# Voltage_Regulator_Design.net
KiCad netlist of a schematic drawn in EAGLE
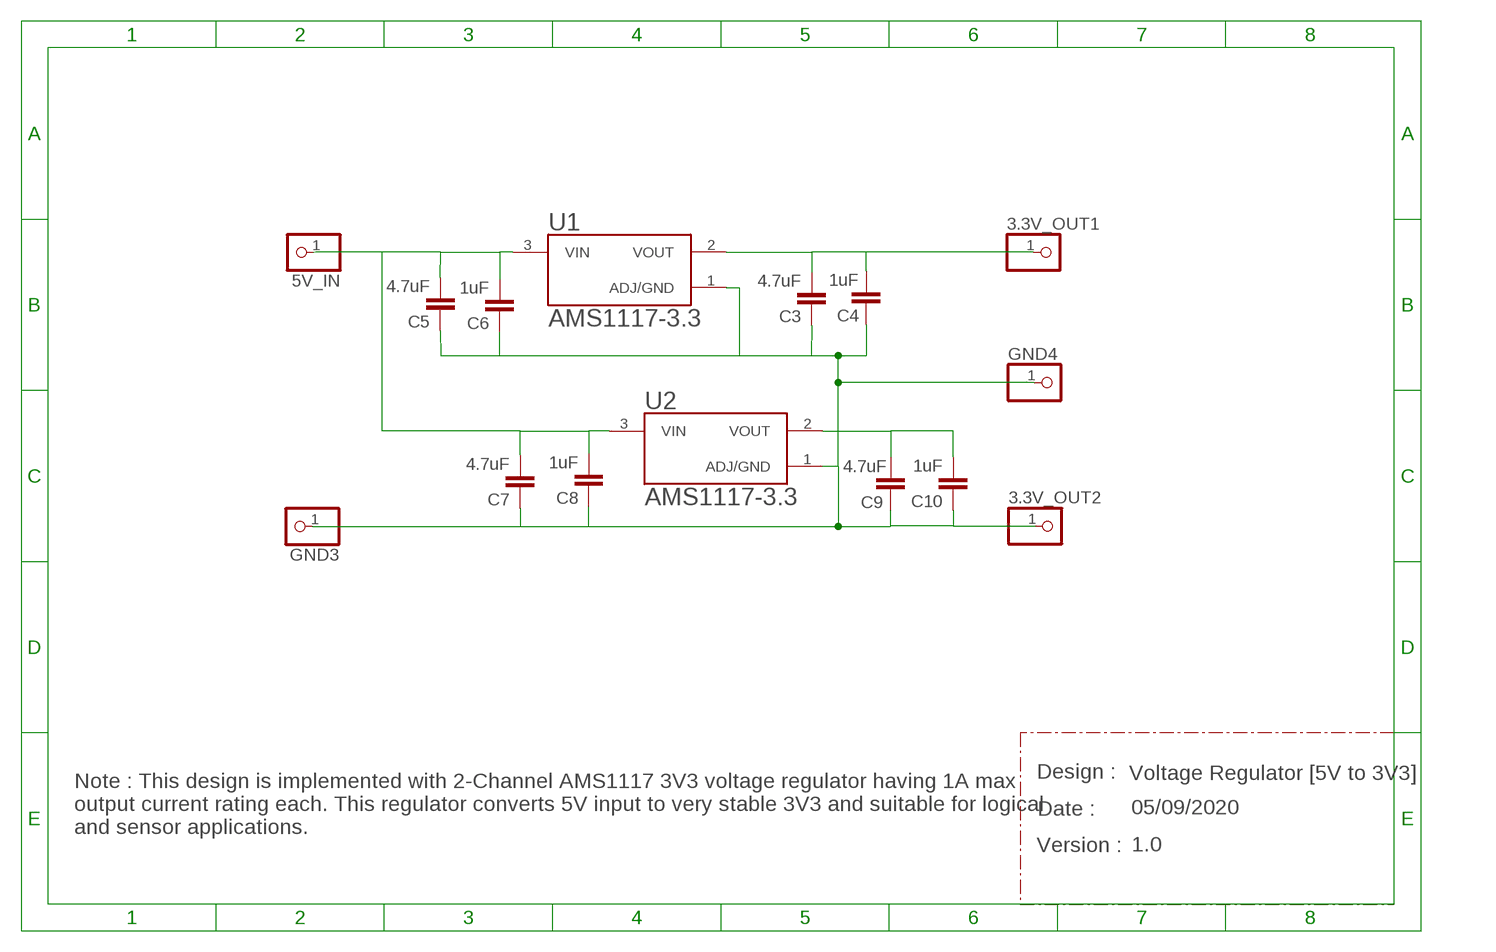
[diagram p0: schematic, sheet 1]

(export (version "E")
  (design (tool "Eeschema 10.0.6"))
  (components
    (comp (ref "3.3V_OUT1")
      (value "PINHD-1X1")
      (footprint "eagle-import:1X01")
      (libsource (lib "eagle-import") (part "PINHD-1X1"))
    )
    (comp (ref "3.3V_OUT2")
      (value "PINHD-1X1")
      (footprint "eagle-import:1X01")
      (libsource (lib "eagle-import") (part "PINHD-1X1"))
    )
    (comp (ref "5V_IN")
      (value "PINHD-1X1")
      (footprint "eagle-import:1X01")
      (libsource (lib "eagle-import") (part "PINHD-1X1"))
    )
    (comp (ref "C3")
      (value "4.7uF")
      (footprint "eagle-import:C0805")
      (libsource (lib "eagle-import") (part "C-EUC0805"))
    )
    (comp (ref "C4")
      (value "1uF")
      (footprint "eagle-import:C0805")
      (libsource (lib "eagle-import") (part "C-EUC0805"))
    )
    (comp (ref "C5")
      (value "4.7uF")
      (footprint "eagle-import:C0805")
      (libsource (lib "eagle-import") (part "C-EUC0805"))
    )
    (comp (ref "C6")
      (value "1uF")
      (footprint "eagle-import:C0805")
      (libsource (lib "eagle-import") (part "C-EUC0805"))
    )
    (comp (ref "C7")
      (value "4.7uF")
      (footprint "eagle-import:C0805")
      (libsource (lib "eagle-import") (part "C-EUC0805"))
    )
    (comp (ref "C8")
      (value "1uF")
      (footprint "eagle-import:C0805")
      (libsource (lib "eagle-import") (part "C-EUC0805"))
    )
    (comp (ref "C9")
      (value "4.7uF")
      (footprint "eagle-import:C0805")
      (libsource (lib "eagle-import") (part "C-EUC0805"))
    )
    (comp (ref "C10")
      (value "1uF")
      (footprint "eagle-import:C0805")
      (libsource (lib "eagle-import") (part "C-EUC0805"))
    )
    (comp (ref "GND3")
      (value "PINHD-1X1")
      (footprint "eagle-import:1X01")
      (libsource (lib "eagle-import") (part "PINHD-1X1"))
    )
    (comp (ref "GND4")
      (value "PINHD-1X1")
      (footprint "eagle-import:1X01")
      (libsource (lib "eagle-import") (part "PINHD-1X1"))
    )
    (comp (ref "U1")
      (value "AMS1117-3.3")
      (footprint "eagle-import:SOT229P700X180-4N")
      (fields (field (name "MF") "Advanced Monolithic Systems"))
      (libsource (lib "eagle-import") (part "AMS1117-3.3"))
    )
    (comp (ref "U2")
      (value "AMS1117-3.3")
      (footprint "eagle-import:SOT229P700X180-4N")
      (fields (field (name "MF") "Advanced Monolithic Systems"))
      (libsource (lib "eagle-import") (part "AMS1117-3.3"))
    )
  )
  (nets
    (net (code "1") (name "Net-(U1-ADJ{slash}GND)") (class "Default")
      (node (ref "3.3V_OUT2") (pin "1") (pinfunction "1_1") (pintype "passive"))
      (node (ref "C10") (pin "1") (pinfunction "1_1") (pintype "passive"))
      (node (ref "C4") (pin "1") (pinfunction "1_1") (pintype "passive"))
      (node (ref "C5") (pin "1") (pinfunction "1_1") (pintype "passive"))
      (node (ref "C6") (pin "1") (pinfunction "1_1") (pintype "passive"))
      (node (ref "C7") (pin "1") (pinfunction "1_1") (pintype "passive"))
      (node (ref "C8") (pin "1") (pinfunction "1_1") (pintype "passive"))
      (node (ref "C9") (pin "1") (pinfunction "1_1") (pintype "passive"))
      (node (ref "GND3") (pin "1") (pinfunction "1_1") (pintype "passive"))
      (node (ref "GND4") (pin "1") (pinfunction "1_1") (pintype "passive"))
      (node (ref "U1") (pin "1") (pinfunction "ADJ/GND_1") (pintype "power_in"))
      (node (ref "U2") (pin "1") (pinfunction "ADJ/GND_1") (pintype "power_in"))
    )
    (net (code "2") (name "Net-(U1-VIN)") (class "Default")
      (node (ref "5V_IN") (pin "1") (pinfunction "1_1") (pintype "passive"))
      (node (ref "C5") (pin "2") (pinfunction "2_2") (pintype "passive"))
      (node (ref "C6") (pin "2") (pinfunction "2_2") (pintype "passive"))
      (node (ref "C7") (pin "2") (pinfunction "2_2") (pintype "passive"))
      (node (ref "C8") (pin "2") (pinfunction "2_2") (pintype "passive"))
      (node (ref "U1") (pin "3") (pinfunction "VIN_3") (pintype "input"))
      (node (ref "U2") (pin "3") (pinfunction "VIN_3") (pintype "input"))
    )
    (net (code "3") (name "Net-(U1-VOUT)") (class "Default")
      (node (ref "3.3V_OUT1") (pin "1") (pinfunction "1_1") (pintype "passive"))
      (node (ref "C3") (pin "2") (pinfunction "2_2") (pintype "passive"))
      (node (ref "C4") (pin "2") (pinfunction "2_2") (pintype "passive"))
      (node (ref "U1") (pin "2") (pinfunction "VOUT_2") (pintype "output"))
    )
    (net (code "4") (name "Net-(U2-VOUT)") (class "Default")
      (node (ref "C10") (pin "2") (pinfunction "2_2") (pintype "passive"))
      (node (ref "C9") (pin "2") (pinfunction "2_2") (pintype "passive"))
      (node (ref "U2") (pin "2") (pinfunction "VOUT_2") (pintype "output"))
    )
    (net (code "5") (name "unconnected-(C3-Pad1)") (class "Default")
      (node (ref "C3") (pin "1") (pinfunction "1_1") (pintype "passive"))
    )
  )
)
